# PROC051C_VPP_Supply.net
KiCad netlist of a schematic drawn in Altium Designer
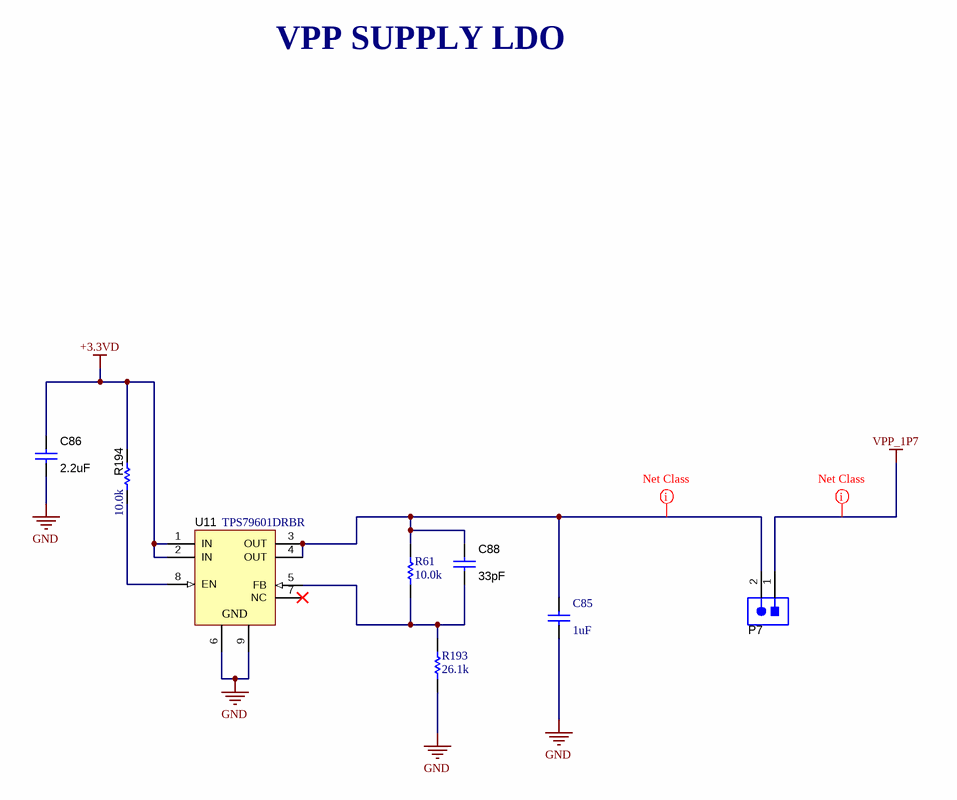
[diagram p0: PROC051C_VPP_Supply.SchDoc]

(export (version "E")
  (design (tool "Eeschema 10.0.6"))
  (components
    (comp (ref "C85")
      (value "GRM155R70J105MA12D")
      (footprint "0402")
      (description "CAP, CERM, 1 uF, 6.3 V, +/- 20%, X7R, 0402")
      (fields
        (field (name "MANUFACTURER") "MuRata")
        (field (name "VALUEDISPLAYED") "1uF")
        (field (name "PUBLISHER") "Texas Instruments")
      )
      (libsource (lib "Altium Vault - TI") (part "Capacitor"))
    )
    (comp (ref "C86")
      (value "C1005X7S1A225K050BC")
      (footprint "0402_065L")
      (description "CAP, CERM, 2.2 uF, 10 V, +/- 10%, X7S, 0402")
      (fields
        (field (name "MANUFACTURER") "TDK")
        (field (name "VALUEDISPLAYED") "2.2uF")
        (field (name "PUBLISHER") "Texas Instruments")
      )
      (libsource (lib "Altium Vault - TI") (part "CMP-0006302-2"))
    )
    (comp (ref "C88")
      (value "C0402C330J5GAC")
      (footprint "0402L")
      (description "CAP, CERM, 33 pF, 50 V, +/- 5%, C0G/NP0, 0402")
      (fields
        (field (name "MANUFACTURER") "Kemet")
        (field (name "VALUEDISPLAYED") "33pF")
        (field (name "PUBLISHER") "Texas Instruments")
      )
      (libsource (lib "Altium Vault - TI") (part "Capacitor"))
    )
    (comp (ref "P7")
      (value "TSW-102-07-G-S")
      (footprint "TSW-102-07-G-S")
      (description "Header, 100mil, 2x1, Gold, TH")
      (fields (field (name "MANUFACTURER") "Samtec"))
      (libsource (lib "Altium Vault - TI") (part "Header_2x1"))
    )
    (comp (ref "R61")
      (value "ERJ-2RKF1002X")
      (footprint "0402")
      (description "RES, 10.0 k, 1%, 0.1 W, 0402")
      (fields
        (field (name "MANUFACTURER") "Panasonic")
        (field (name "VALUEDISPLAYED") "10.0k")
        (field (name "PUBLISHER") "Texas Instruments")
      )
      (libsource (lib "Altium Vault - TI") (part "Resistor"))
    )
    (comp (ref "R193")
      (value "CRCW040226K1FKED")
      (footprint "0402")
      (description "RES, 26.1 k, 1%, 0.063 W, AEC-Q200 Grade 0, 0402")
      (fields (field (name "MANUFACTURER") "Vishay-Dale") (field (name "VALUEDISPLAYED") "26.1k"))
      (libsource (lib "Altium Vault - TI") (part "Resistor"))
    )
    (comp (ref "R194")
      (value "CRCW040210K0FKED")
      (footprint "0402L")
      (description "RES, 10.0 k, 1%, 0.063 W, AEC-Q200 Grade 0, 0402")
      (fields (field (name "MANUFACTURER") "Vishay-Dale") (field (name "VALUEDISPLAYED") "10.0k"))
      (libsource (lib "Altium Vault - TI") (part "Resistor"))
    )
    (comp (ref "U11")
      (value "TPS79601DRBR")
      (footprint "DRB0008B")
      (fields (field (name "MANUFACTURER") "Texas Instruments") (field (name "PARTNUMBER") "TPS79601DRBR"))
      (libsource (lib "Altium Vault - TI") (part "CMP-0036402-3"))
    )
  )
  (nets
    (net (code "1") (name "+3.3VD") (class "Default")
      (node (ref "C86") (pin "2") (pinfunction "2_2") (pintype "passive"))
      (node (ref "R194") (pin "1") (pinfunction "1_1") (pintype "passive"))
      (node (ref "U11") (pin "1") (pinfunction "IN_1") (pintype "power_in"))
      (node (ref "U11") (pin "2") (pinfunction "IN_2") (pintype "power_in"))
    )
    (net (code "2") (name "GND") (class "Default")
      (node (ref "C85") (pin "2") (pinfunction "2_2") (pintype "passive"))
      (node (ref "C86") (pin "1") (pinfunction "1_1") (pintype "passive"))
      (node (ref "R193") (pin "1") (pinfunction "1_1") (pintype "passive"))
      (node (ref "U11") (pin "6") (pinfunction "GND_6") (pintype "power_in"))
      (node (ref "U11") (pin "9") (pinfunction "GND_9") (pintype "power_in"))
    )
    (net (code "3") (name "Net-(C85-Pad1)") (class "Default")
      (node (ref "C85") (pin "1") (pinfunction "1_1") (pintype "passive"))
      (node (ref "C88") (pin "1") (pinfunction "1_1") (pintype "passive"))
      (node (ref "P7") (pin "2") (pinfunction "2_2") (pintype "passive"))
      (node (ref "R61") (pin "2") (pinfunction "2_2") (pintype "passive"))
      (node (ref "U11") (pin "3") (pinfunction "OUT_3") (pintype "power_in"))
      (node (ref "U11") (pin "4") (pinfunction "OUT_4") (pintype "power_in"))
    )
    (net (code "4") (name "Net-(U11-EN)") (class "Default")
      (node (ref "R194") (pin "2") (pinfunction "2_2") (pintype "passive"))
      (node (ref "U11") (pin "8") (pinfunction "EN_8") (pintype "input"))
    )
    (net (code "5") (name "Net-(U11-FB)") (class "Default")
      (node (ref "C88") (pin "2") (pinfunction "2_2") (pintype "passive"))
      (node (ref "R193") (pin "2") (pinfunction "2_2") (pintype "passive"))
      (node (ref "R61") (pin "1") (pinfunction "1_1") (pintype "passive"))
      (node (ref "U11") (pin "5") (pinfunction "FB_5") (pintype "input"))
    )
    (net (code "6") (name "VPP_1P7") (class "Default")
      (node (ref "P7") (pin "1") (pinfunction "1_1") (pintype "passive"))
    )
    (net (code "7") (name "unconnected-(U11-NC-Pad7)") (class "Default")
      (node (ref "U11") (pin "7") (pinfunction "NC_7") (pintype "passive+no_connect"))
    )
  )
)
